# VT_adapter.net
KiCad netlist of a schematic drawn in EAGLE
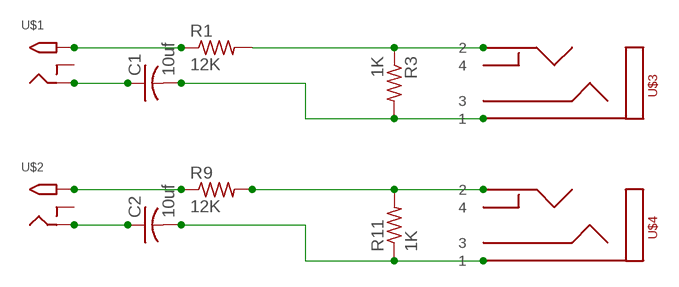
[diagram p0: schematic, sheet 1]

(export (version "E")
  (design (tool "Eeschema 10.0.6"))
  (components
    (comp (ref "C1")
      (value "10uf")
      (footprint "eagle-import:C1206")
      (libsource (lib "eagle-import") (part "C-USC1206"))
    )
    (comp (ref "C2")
      (value "10uf")
      (footprint "eagle-import:C1206")
      (libsource (lib "eagle-import") (part "C-USC1206"))
    )
    (comp (ref "R1")
      (value "12K")
      (footprint "eagle-import:R1206")
      (libsource (lib "eagle-import") (part "R-US_R1206"))
    )
    (comp (ref "R3")
      (value "1K")
      (footprint "eagle-import:R1206")
      (libsource (lib "eagle-import") (part "R-US_R1206"))
    )
    (comp (ref "R9")
      (value "12K")
      (footprint "eagle-import:R1206")
      (libsource (lib "eagle-import") (part "R-US_R1206"))
    )
    (comp (ref "R11")
      (value "1K")
      (footprint "eagle-import:R1206")
      (libsource (lib "eagle-import") (part "R-US_R1206"))
    )
    (comp (ref "U$1")
      (value "2.1MMJACKSMT")
      (footprint "eagle-import:DCJACK_2MM_SMT")
      (libsource (lib "eagle-import") (part "2.1MMJACKSMT"))
    )
    (comp (ref "U$2")
      (value "2.1MMJACKSMT")
      (footprint "eagle-import:DCJACK_2MM_SMT")
      (libsource (lib "eagle-import") (part "2.1MMJACKSMT"))
    )
    (comp (ref "U$3")
      (value "STEREO_SMD")
      (footprint "eagle-import:STEREO_SMT")
      (libsource (lib "eagle-import") (part "STEREO_SMD"))
    )
    (comp (ref "U$4")
      (value "STEREO_SMD")
      (footprint "eagle-import:STEREO_SMT")
      (libsource (lib "eagle-import") (part "STEREO_SMD"))
    )
  )
  (nets
    (net (code "1") (name "Net-(U$1-RING)") (class "Default")
      (node (ref "C1") (pin "1") (pinfunction "1_1") (pintype "passive"))
      (node (ref "U$1") (pin "GND") (pinfunction "RING_GND") (pintype "bidirectional"))
    )
    (net (code "2") (name "Net-(U$1-TIP)") (class "Default")
      (node (ref "R1") (pin "1") (pinfunction "1_1") (pintype "passive"))
      (node (ref "U$1") (pin "PWR2") (pinfunction "TIP_PWR2") (pintype "bidirectional"))
    )
    (net (code "3") (name "Net-(U$2-RING)") (class "Default")
      (node (ref "C2") (pin "1") (pinfunction "1_1") (pintype "passive"))
      (node (ref "U$2") (pin "GND") (pinfunction "RING_GND") (pintype "bidirectional"))
    )
    (net (code "4") (name "Net-(U$2-TIP)") (class "Default")
      (node (ref "R9") (pin "1") (pinfunction "1_1") (pintype "passive"))
      (node (ref "U$2") (pin "PWR2") (pinfunction "TIP_PWR2") (pintype "bidirectional"))
    )
    (net (code "5") (name "Net-(U$3-1)") (class "Default")
      (node (ref "C1") (pin "2") (pinfunction "2_2") (pintype "passive"))
      (node (ref "R3") (pin "2") (pinfunction "2_2") (pintype "passive"))
      (node (ref "U$3") (pin "P$1") (pinfunction "1_P$1") (pintype "bidirectional"))
    )
    (net (code "6") (name "Net-(U$3-2)") (class "Default")
      (node (ref "R1") (pin "2") (pinfunction "2_2") (pintype "passive"))
      (node (ref "R3") (pin "1") (pinfunction "1_1") (pintype "passive"))
      (node (ref "U$3") (pin "P$2") (pinfunction "2_P$2") (pintype "bidirectional"))
    )
    (net (code "7") (name "Net-(U$4-1)") (class "Default")
      (node (ref "C2") (pin "2") (pinfunction "2_2") (pintype "passive"))
      (node (ref "R11") (pin "1") (pinfunction "1_1") (pintype "passive"))
      (node (ref "U$4") (pin "P$1") (pinfunction "1_P$1") (pintype "bidirectional"))
    )
    (net (code "8") (name "Net-(U$4-2)") (class "Default")
      (node (ref "R11") (pin "2") (pinfunction "2_2") (pintype "passive"))
      (node (ref "R9") (pin "2") (pinfunction "2_2") (pintype "passive"))
      (node (ref "U$4") (pin "P$2") (pinfunction "2_P$2") (pintype "bidirectional"))
    )
    (net (code "9") (name "unconnected-(U$1-RING_SW-PadGNDBREAK)") (class "Default")
      (node (ref "U$1") (pin "GNDBREAK") (pinfunction "RING_SW_GNDBREAK") (pintype "bidirectional"))
    )
    (net (code "10") (name "unconnected-(U$2-RING_SW-PadGNDBREAK)") (class "Default")
      (node (ref "U$2") (pin "GNDBREAK") (pinfunction "RING_SW_GNDBREAK") (pintype "bidirectional"))
    )
    (net (code "11") (name "unconnected-(U$3-3-PadP$3)") (class "Default")
      (node (ref "U$3") (pin "P$3") (pinfunction "3_P$3") (pintype "bidirectional"))
    )
    (net (code "12") (name "unconnected-(U$3-4-PadP$4)") (class "Default")
      (node (ref "U$3") (pin "P$4") (pinfunction "4_P$4") (pintype "bidirectional"))
    )
    (net (code "13") (name "unconnected-(U$4-3-PadP$3)") (class "Default")
      (node (ref "U$4") (pin "P$3") (pinfunction "3_P$3") (pintype "bidirectional"))
    )
    (net (code "14") (name "unconnected-(U$4-4-PadP$4)") (class "Default")
      (node (ref "U$4") (pin "P$4") (pinfunction "4_P$4") (pintype "bidirectional"))
    )
  )
)
